# bat-off-on-threshold-voltage_v1.net
KiCad netlist of a schematic drawn in EAGLE
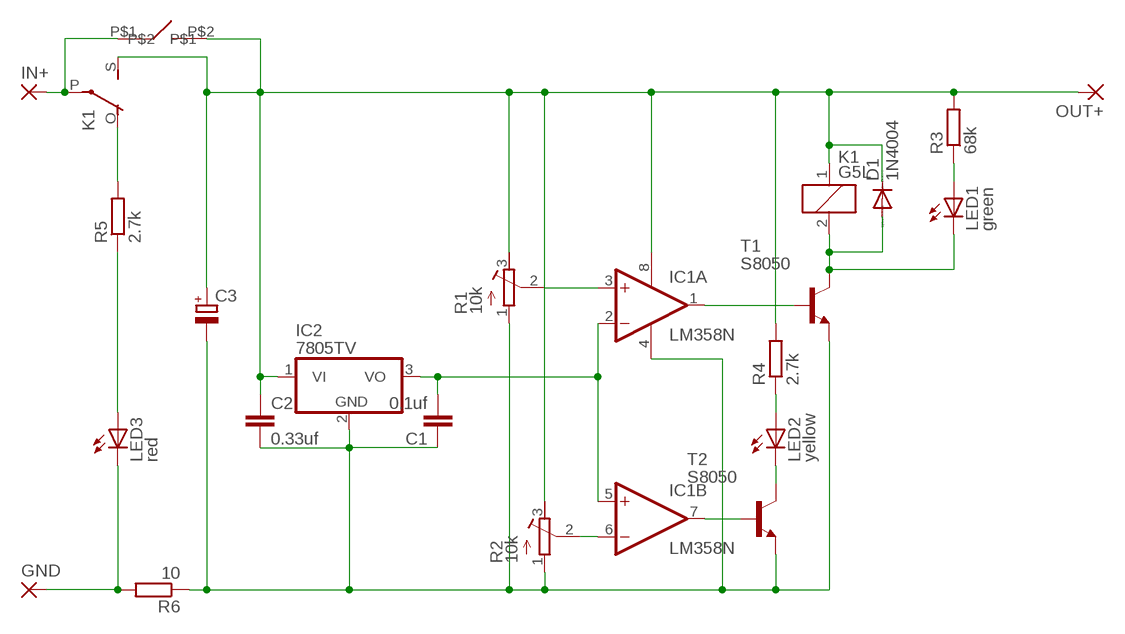
[diagram p0: schematic, sheet 1]

(export (version "E")
  (design (tool "Eeschema 10.0.6"))
  (components
    (comp (ref "C1")
      (value "0.1uf")
      (footprint "eagle-import:C050-025X075")
      (libsource (lib "eagle-import") (part "C-EU050-025X075"))
    )
    (comp (ref "C2")
      (value "0.33uf")
      (footprint "eagle-import:C050-025X075")
      (libsource (lib "eagle-import") (part "C-EU050-025X075"))
    )
    (comp (ref "C3")
      (value "CPOL-EUE2.5-6")
      (footprint "eagle-import:E2,5-6")
      (libsource (lib "eagle-import") (part "CPOL-EUE2.5-6"))
    )
    (comp (ref "D1")
      (value "1N4004")
      (footprint "eagle-import:DO41-10")
      (libsource (lib "eagle-import") (part "1N4004"))
    )
    (comp (ref "GND")
      (value "3,81/1,1")
      (footprint "eagle-import:3,81_1,1")
      (libsource (lib "eagle-import") (part "3,81/1,1"))
    )
    (comp (ref "IC1")
      (value "LM358N")
      (footprint "eagle-import:DIL08")
      (libsource (lib "eagle-import") (part "LM358N"))
    )
    (comp (ref "IC2")
      (value "7805TV")
      (footprint "eagle-import:TO220V")
      (libsource (lib "eagle-import") (part "78TV05"))
    )
    (comp (ref "IN+")
      (value "3,81/1,1")
      (footprint "eagle-import:3,81_1,1")
      (libsource (lib "eagle-import") (part "3,81/1,1"))
    )
    (comp (ref "K1")
      (value "G5L")
      (footprint "eagle-import:G5LE")
      (libsource (lib "eagle-import") (part "G5L"))
    )
    (comp (ref "LED1")
      (value "green")
      (footprint "eagle-import:LED3MM")
      (libsource (lib "eagle-import") (part "LED3MM"))
    )
    (comp (ref "LED2")
      (value "yellow")
      (footprint "eagle-import:LED3MM")
      (libsource (lib "eagle-import") (part "LED3MM"))
    )
    (comp (ref "LED3")
      (value "red")
      (footprint "eagle-import:LED3MM")
      (libsource (lib "eagle-import") (part "LED3MM"))
    )
    (comp (ref "OUT+")
      (value "3,81/1,1")
      (footprint "eagle-import:3,81_1,1")
      (libsource (lib "eagle-import") (part "3,81/1,1"))
    )
    (comp (ref "R1")
      (value "10k")
      (footprint "eagle-import:RTRIM3296W")
      (libsource (lib "eagle-import") (part "R-TRIMM3296W"))
    )
    (comp (ref "R2")
      (value "10k")
      (footprint "eagle-import:RTRIM3296W")
      (libsource (lib "eagle-import") (part "R-TRIMM3296W"))
    )
    (comp (ref "R3")
      (value "68k")
      (footprint "eagle-import:0204_7")
      (libsource (lib "eagle-import") (part "R-EU_0204/7"))
    )
    (comp (ref "R4")
      (value "2.7k")
      (footprint "eagle-import:0204_7")
      (libsource (lib "eagle-import") (part "R-EU_0204/7"))
    )
    (comp (ref "R5")
      (value "2.7k")
      (footprint "eagle-import:0204_7")
      (libsource (lib "eagle-import") (part "R-EU_0204/7"))
    )
    (comp (ref "R6")
      (value "10")
      (footprint "eagle-import:0204_7")
      (libsource (lib "eagle-import") (part "R-EU_0204/7"))
    )
    (comp (ref "T1")
      (value "S8050")
      (footprint "eagle-import:TO92-EBC")
      (libsource (lib "eagle-import") (part "-NPN-TO92-EBC"))
    )
    (comp (ref "T2")
      (value "S8050")
      (footprint "eagle-import:TO92-EBC")
      (libsource (lib "eagle-import") (part "-NPN-TO92-EBC"))
    )
    (comp (ref "U$1")
      (value "BTN-6X6")
      (footprint "eagle-import:BTN-6X6")
      (libsource (lib "eagle-import") (part "BTN-6X6"))
    )
  )
  (nets
    (net (code "1") (name "Net-(GND-P)") (class "Default")
      (node (ref "GND") (pin "1") (pinfunction "P_1") (pintype "passive"))
      (node (ref "LED3") (pin "K") (pinfunction "C_K") (pintype "passive"))
      (node (ref "R6") (pin "2") (pinfunction "2_2") (pintype "passive"))
    )
    (net (code "2") (name "Net-(IC1A-+IN)") (class "Default")
      (node (ref "IC1") (pin "3") (pinfunction "+IN_3") (pintype "input"))
      (node (ref "R1") (pin "2") (pinfunction "S_2") (pintype "passive"))
    )
    (net (code "3") (name "Net-(IC1A--IN)") (class "Default")
      (node (ref "C1") (pin "2") (pinfunction "2_2") (pintype "passive"))
      (node (ref "IC1") (pin "2") (pinfunction "-IN_2") (pintype "input"))
      (node (ref "IC1") (pin "5") (pinfunction "+IN_5") (pintype "input"))
      (node (ref "IC2") (pin "3") (pinfunction "VO_3") (pintype "passive"))
    )
    (net (code "4") (name "Net-(IC1A-OUT)") (class "Default")
      (node (ref "IC1") (pin "1") (pinfunction "OUT_1") (pintype "output"))
      (node (ref "T1") (pin "B") (pinfunction "B_B") (pintype "passive"))
    )
    (net (code "5") (name "Net-(IC1B--IN)") (class "Default")
      (node (ref "IC1") (pin "6") (pinfunction "-IN_6") (pintype "input"))
      (node (ref "R2") (pin "2") (pinfunction "S_2") (pintype "passive"))
    )
    (net (code "6") (name "Net-(IC1B-OUT)") (class "Default")
      (node (ref "IC1") (pin "7") (pinfunction "OUT_7") (pintype "output"))
      (node (ref "T2") (pin "B") (pinfunction "B_B") (pintype "passive"))
    )
    (net (code "7") (name "Net-(IC1C-V+)") (class "Default")
      (node (ref "C2") (pin "1") (pinfunction "1_1") (pintype "passive"))
      (node (ref "C3") (pin "+") (pinfunction "+_+") (pintype "passive"))
      (node (ref "D1") (pin "C") (pinfunction "C_C") (pintype "passive"))
      (node (ref "IC1") (pin "8") (pinfunction "V+_8") (pintype "power_in"))
      (node (ref "IC2") (pin "1") (pinfunction "VI_1") (pintype "input"))
      (node (ref "K1") (pin "1") (pinfunction "1_1") (pintype "passive"))
      (node (ref "K1") (pin "S") (pinfunction "S_S") (pintype "passive"))
      (node (ref "OUT+") (pin "1") (pinfunction "P_1") (pintype "passive"))
      (node (ref "R1") (pin "3") (pinfunction "E_3") (pintype "passive"))
      (node (ref "R2") (pin "3") (pinfunction "E_3") (pintype "passive"))
      (node (ref "R3") (pin "2") (pinfunction "2_2") (pintype "passive"))
      (node (ref "R4") (pin "2") (pinfunction "2_2") (pintype "passive"))
      (node (ref "U$1") (pin "P$2") (pinfunction "P$2_P$2") (pintype "bidirectional"))
    )
    (net (code "8") (name "Net-(IC1C-V-)") (class "Default")
      (node (ref "C1") (pin "1") (pinfunction "1_1") (pintype "passive"))
      (node (ref "C2") (pin "2") (pinfunction "2_2") (pintype "passive"))
      (node (ref "C3") (pin "-") (pinfunction "-_-") (pintype "passive"))
      (node (ref "IC1") (pin "4") (pinfunction "V-_4") (pintype "power_in"))
      (node (ref "IC2") (pin "2") (pinfunction "GND_2") (pintype "passive"))
      (node (ref "R1") (pin "1") (pinfunction "A_1") (pintype "passive"))
      (node (ref "R2") (pin "1") (pinfunction "A_1") (pintype "passive"))
      (node (ref "R6") (pin "1") (pinfunction "1_1") (pintype "passive"))
      (node (ref "T1") (pin "E") (pinfunction "E_E") (pintype "passive"))
      (node (ref "T2") (pin "E") (pinfunction "E_E") (pintype "passive"))
    )
    (net (code "9") (name "Net-(IN+-P)") (class "Default")
      (node (ref "IN+") (pin "1") (pinfunction "P_1") (pintype "passive"))
      (node (ref "K1") (pin "P") (pinfunction "P_P") (pintype "passive"))
      (node (ref "U$1") (pin "P$1") (pinfunction "P$1_P$1") (pintype "bidirectional"))
    )
    (net (code "10") (name "Net-(K1-PadO)") (class "Default")
      (node (ref "K1") (pin "O") (pinfunction "O_O") (pintype "passive"))
      (node (ref "R5") (pin "2") (pinfunction "2_2") (pintype "passive"))
    )
    (net (code "11") (name "Net-(LED1-C)") (class "Default")
      (node (ref "D1") (pin "A") (pinfunction "A_A") (pintype "passive"))
      (node (ref "K1") (pin "2") (pinfunction "2_2") (pintype "passive"))
      (node (ref "LED1") (pin "K") (pinfunction "C_K") (pintype "passive"))
      (node (ref "T1") (pin "C") (pinfunction "C_C") (pintype "passive"))
    )
    (net (code "12") (name "Net-(LED1-PadA)") (class "Default")
      (node (ref "LED1") (pin "A") (pinfunction "A_A") (pintype "passive"))
      (node (ref "R3") (pin "1") (pinfunction "1_1") (pintype "passive"))
    )
    (net (code "13") (name "Net-(LED2-C)") (class "Default")
      (node (ref "LED2") (pin "K") (pinfunction "C_K") (pintype "passive"))
      (node (ref "T2") (pin "C") (pinfunction "C_C") (pintype "passive"))
    )
    (net (code "14") (name "Net-(LED2-PadA)") (class "Default")
      (node (ref "LED2") (pin "A") (pinfunction "A_A") (pintype "passive"))
      (node (ref "R4") (pin "1") (pinfunction "1_1") (pintype "passive"))
    )
    (net (code "15") (name "Net-(LED3-PadA)") (class "Default")
      (node (ref "LED3") (pin "A") (pinfunction "A_A") (pintype "passive"))
      (node (ref "R5") (pin "1") (pinfunction "1_1") (pintype "passive"))
    )
  )
)
